# PSX-PS2.net
KiCad netlist of a schematic drawn in EAGLE
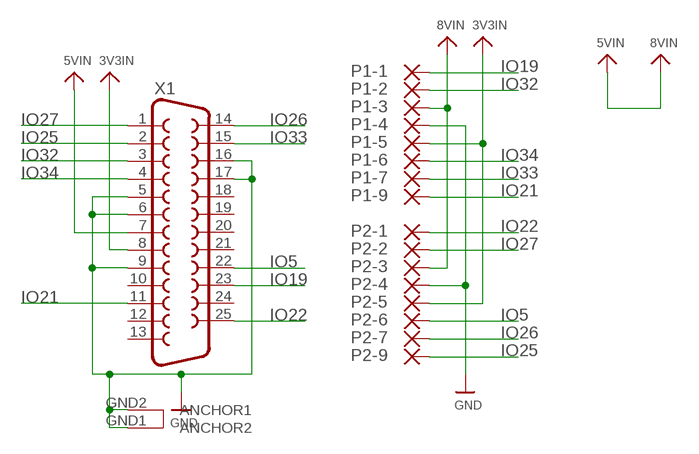
[diagram p0: schematic, sheet 1]

(export (version "E")
  (design (tool "Eeschema 10.0.6"))
  (components
    (comp (ref "P1-1")
      (value "SMD5")
      (footprint "eagle-import:SMD2,54-5,08")
      (libsource (lib "eagle-import") (part "SMD5"))
    )
    (comp (ref "P1-2")
      (value "SMD5")
      (footprint "eagle-import:SMD2,54-5,08")
      (libsource (lib "eagle-import") (part "SMD5"))
    )
    (comp (ref "P1-3")
      (value "SMD5")
      (footprint "eagle-import:SMD2,54-5,08")
      (libsource (lib "eagle-import") (part "SMD5"))
    )
    (comp (ref "P1-4")
      (value "SMD5")
      (footprint "eagle-import:SMD2,54-5,08")
      (libsource (lib "eagle-import") (part "SMD5"))
    )
    (comp (ref "P1-5")
      (value "SMD5")
      (footprint "eagle-import:SMD2,54-5,08")
      (libsource (lib "eagle-import") (part "SMD5"))
    )
    (comp (ref "P1-6")
      (value "SMD5")
      (footprint "eagle-import:SMD2,54-5,08")
      (libsource (lib "eagle-import") (part "SMD5"))
    )
    (comp (ref "P1-7")
      (value "SMD5")
      (footprint "eagle-import:SMD2,54-5,08")
      (libsource (lib "eagle-import") (part "SMD5"))
    )
    (comp (ref "P1-9")
      (value "SMD5")
      (footprint "eagle-import:SMD2,54-5,08")
      (libsource (lib "eagle-import") (part "SMD5"))
    )
    (comp (ref "P2-1")
      (value "SMD5")
      (footprint "eagle-import:SMD2,54-5,08")
      (libsource (lib "eagle-import") (part "SMD5"))
    )
    (comp (ref "P2-2")
      (value "SMD5")
      (footprint "eagle-import:SMD2,54-5,08")
      (libsource (lib "eagle-import") (part "SMD5"))
    )
    (comp (ref "P2-3")
      (value "SMD5")
      (footprint "eagle-import:SMD2,54-5,08")
      (libsource (lib "eagle-import") (part "SMD5"))
    )
    (comp (ref "P2-4")
      (value "SMD5")
      (footprint "eagle-import:SMD2,54-5,08")
      (libsource (lib "eagle-import") (part "SMD5"))
    )
    (comp (ref "P2-5")
      (value "SMD5")
      (footprint "eagle-import:SMD2,54-5,08")
      (libsource (lib "eagle-import") (part "SMD5"))
    )
    (comp (ref "P2-6")
      (value "SMD5")
      (footprint "eagle-import:SMD2,54-5,08")
      (libsource (lib "eagle-import") (part "SMD5"))
    )
    (comp (ref "P2-7")
      (value "SMD5")
      (footprint "eagle-import:SMD2,54-5,08")
      (libsource (lib "eagle-import") (part "SMD5"))
    )
    (comp (ref "P2-9")
      (value "SMD5")
      (footprint "eagle-import:SMD2,54-5,08")
      (libsource (lib "eagle-import") (part "SMD5"))
    )
    (comp (ref "X1")
      (value "DB25_FEMALEHP")
      (footprint "eagle-import:F25HP")
      (libsource (lib "eagle-import") (part "DB25_FEMALEHP"))
    )
  )
  (nets
    (net (code "1") (name "/IO5") (class "Default")
      (node (ref "P2-6") (pin "1") (pinfunction "P_1") (pintype "passive"))
      (node (ref "X1") (pin "22") (pinfunction "22_22") (pintype "passive"))
    )
    (net (code "2") (name "/IO19") (class "Default")
      (node (ref "P1-1") (pin "1") (pinfunction "P_1") (pintype "passive"))
      (node (ref "X1") (pin "23") (pinfunction "23_23") (pintype "passive"))
    )
    (net (code "3") (name "/IO21") (class "Default")
      (node (ref "P1-9") (pin "1") (pinfunction "P_1") (pintype "passive"))
      (node (ref "X1") (pin "11") (pinfunction "11_11") (pintype "passive"))
    )
    (net (code "4") (name "/IO22") (class "Default")
      (node (ref "P2-1") (pin "1") (pinfunction "P_1") (pintype "passive"))
      (node (ref "X1") (pin "25") (pinfunction "25_25") (pintype "passive"))
    )
    (net (code "5") (name "/IO25") (class "Default")
      (node (ref "P2-9") (pin "1") (pinfunction "P_1") (pintype "passive"))
      (node (ref "X1") (pin "2") (pinfunction "2_2") (pintype "passive"))
    )
    (net (code "6") (name "/IO26") (class "Default")
      (node (ref "P2-7") (pin "1") (pinfunction "P_1") (pintype "passive"))
      (node (ref "X1") (pin "14") (pinfunction "14_14") (pintype "passive"))
    )
    (net (code "7") (name "/IO27") (class "Default")
      (node (ref "P2-2") (pin "1") (pinfunction "P_1") (pintype "passive"))
      (node (ref "X1") (pin "1") (pinfunction "1_1") (pintype "passive"))
    )
    (net (code "8") (name "/IO32") (class "Default")
      (node (ref "P1-2") (pin "1") (pinfunction "P_1") (pintype "passive"))
      (node (ref "X1") (pin "3") (pinfunction "3_3") (pintype "passive"))
    )
    (net (code "9") (name "/IO33") (class "Default")
      (node (ref "P1-7") (pin "1") (pinfunction "P_1") (pintype "passive"))
      (node (ref "X1") (pin "15") (pinfunction "15_15") (pintype "passive"))
    )
    (net (code "10") (name "/IO34") (class "Default")
      (node (ref "P1-6") (pin "1") (pinfunction "P_1") (pintype "passive"))
      (node (ref "X1") (pin "4") (pinfunction "4_4") (pintype "passive"))
    )
    (net (code "11") (name "3V3IN") (class "Default")
      (node (ref "P1-5") (pin "1") (pinfunction "P_1") (pintype "passive"))
      (node (ref "P2-5") (pin "1") (pinfunction "P_1") (pintype "passive"))
      (node (ref "X1") (pin "8") (pinfunction "8_8") (pintype "passive"))
    )
    (net (code "12") (name "5VIN") (class "Default")
      (node (ref "P1-3") (pin "1") (pinfunction "P_1") (pintype "passive"))
      (node (ref "P2-3") (pin "1") (pinfunction "P_1") (pintype "passive"))
      (node (ref "X1") (pin "7") (pinfunction "7_7") (pintype "passive"))
    )
    (net (code "13") (name "GND") (class "Default")
      (node (ref "P1-4") (pin "1") (pinfunction "P_1") (pintype "passive"))
      (node (ref "P2-4") (pin "1") (pinfunction "P_1") (pintype "passive"))
      (node (ref "X1") (pin "16") (pinfunction "16_16") (pintype "passive"))
      (node (ref "X1") (pin "17") (pinfunction "17_17") (pintype "passive"))
      (node (ref "X1") (pin "5") (pinfunction "5_5") (pintype "passive"))
      (node (ref "X1") (pin "6") (pinfunction "6_6") (pintype "passive"))
      (node (ref "X1") (pin "9") (pinfunction "9_9") (pintype "passive"))
      (node (ref "X1") (pin "GND1") (pinfunction "ANCHOR2_GND1") (pintype "bidirectional"))
      (node (ref "X1") (pin "GND2") (pinfunction "ANCHOR1_GND2") (pintype "bidirectional"))
    )
    (net (code "14") (name "unconnected-(X1-Pad10)") (class "Default")
      (node (ref "X1") (pin "10") (pinfunction "10_10") (pintype "passive"))
    )
    (net (code "15") (name "unconnected-(X1-Pad12)") (class "Default")
      (node (ref "X1") (pin "12") (pinfunction "12_12") (pintype "passive"))
    )
    (net (code "16") (name "unconnected-(X1-Pad13)") (class "Default")
      (node (ref "X1") (pin "13") (pinfunction "13_13") (pintype "passive"))
    )
    (net (code "17") (name "unconnected-(X1-Pad18)") (class "Default")
      (node (ref "X1") (pin "18") (pinfunction "18_18") (pintype "passive"))
    )
    (net (code "18") (name "unconnected-(X1-Pad19)") (class "Default")
      (node (ref "X1") (pin "19") (pinfunction "19_19") (pintype "passive"))
    )
    (net (code "19") (name "unconnected-(X1-Pad20)") (class "Default")
      (node (ref "X1") (pin "20") (pinfunction "20_20") (pintype "passive"))
    )
    (net (code "20") (name "unconnected-(X1-Pad21)") (class "Default")
      (node (ref "X1") (pin "21") (pinfunction "21_21") (pintype "passive"))
    )
    (net (code "21") (name "unconnected-(X1-Pad24)") (class "Default")
      (node (ref "X1") (pin "24") (pinfunction "24_24") (pintype "passive"))
    )
  )
)
